# Accumulator_DC-DC.net
KiCad netlist of a schematic drawn in Altium Designer
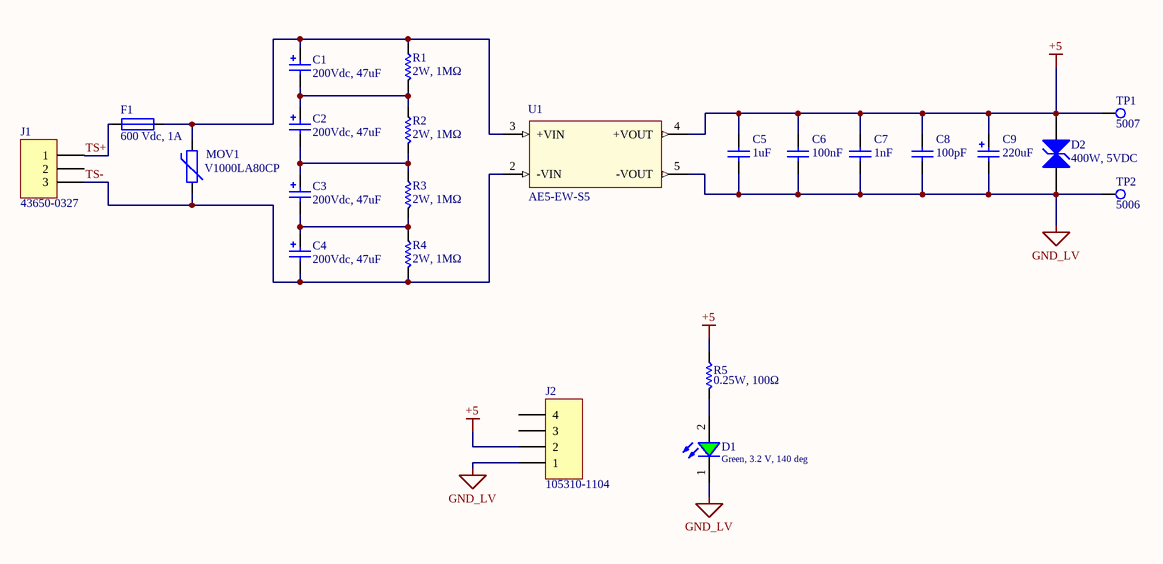
[diagram p0: Accumulator_DC-DC.SchDoc]

(export (version "E")
  (design (tool "Eeschema 10.0.6"))
  (components
    (comp (ref "C1")
      (value "200Vdc, 47uF")
      (footprint "WCAP-AT1H_13x20x5")
      (description "WCAP-AT1H Aluminum Electrolytic Capacitors, size Ф13x20mm, 200V DC, 47uF")
      (fields (field (name "PART NUMBER") "860241078002") (field (name "PUBLISHER") "Wurth Elektronik"))
      (libsource (lib "Components_Library") (part "860241078002"))
    )
    (comp (ref "C2")
      (value "200Vdc, 47uF")
      (footprint "WCAP-AT1H_13x20x5")
      (description "WCAP-AT1H Aluminum Electrolytic Capacitors, size Ф13x20mm, 200V DC, 47uF")
      (fields (field (name "PART NUMBER") "860241078002") (field (name "PUBLISHER") "Wurth Elektronik"))
      (libsource (lib "Components_Library") (part "860241078002"))
    )
    (comp (ref "C3")
      (value "200Vdc, 47uF")
      (footprint "WCAP-AT1H_13x20x5")
      (description "WCAP-AT1H Aluminum Electrolytic Capacitors, size Ф13x20mm, 200V DC, 47uF")
      (fields (field (name "PART NUMBER") "860241078002") (field (name "PUBLISHER") "Wurth Elektronik"))
      (libsource (lib "Components_Library") (part "860241078002"))
    )
    (comp (ref "C4")
      (value "200Vdc, 47uF")
      (footprint "WCAP-AT1H_13x20x5")
      (description "WCAP-AT1H Aluminum Electrolytic Capacitors, size Ф13x20mm, 200V DC, 47uF")
      (fields (field (name "PART NUMBER") "860241078002") (field (name "PUBLISHER") "Wurth Elektronik"))
      (libsource (lib "Components_Library") (part "860241078002"))
    )
    (comp (ref "C5")
      (value "1uF")
      (footprint "1206_3.2x1.6x1.15mm")
      (description "WCAP-CSGP Ceramic Capacitors, 1206, X7R, 10V, 1uF")
      (fields (field (name "PART NUMBER") "885012208013") (field (name "MANUFACTURER") "Wurth Elektronik"))
      (libsource (lib "Components_Library") (part "885012208013"))
    )
    (comp (ref "C6")
      (value "100nF")
      (footprint "1206_3.2x1.6x0.8mm")
      (description "WCAP-CSGP Ceramic Capacitors, 1206, X7R, 10V, 100nF")
      (fields (field (name "PART NUMBER") "885012208009") (field (name "MANUFACTURER") "Wurth Elektronik"))
      (libsource (lib "Components_Library") (part "885012208009"))
    )
    (comp (ref "C7")
      (value "1nF")
      (footprint "1206_3.2x1.6x0.8mm")
      (description "WCAP-CSGP Ceramic Capacitors, 1206, X7R, 10V, 1nF")
      (fields (field (name "PART NUMBER") "885012208006") (field (name "MANUFACTURER") "Wurth Elektronik"))
      (libsource (lib "Components_Library") (part "885012208006"))
    )
    (comp (ref "C8")
      (value "100pF")
      (footprint "1206_3.2x1.6x0.8mm")
      (description "WCAP-CSGP Ceramic Capacitors, 1206, NP0, 10V, 100pF")
      (fields (field (name "PART NUMBER") "885012008004") (field (name "MANUFACTURER") "Wurth Elektronik"))
      (libsource (lib "Components_Library") (part "885012008004"))
    )
    (comp (ref "C9")
      (value "220uF")
      (footprint "WCAP-ATG8_6.3x11x2.5")
      (description "WCAP-ATG8 Aluminum Electrolytic Capacitors, 6.3x11mm, 10 Vdc, 220 uF")
      (fields (field (name "PART NUMBER") "860010273009") (field (name "MANUFACTURER") "Wurth Elektronik"))
      (libsource (lib "Components_Library") (part "860010273009"))
    )
    (comp (ref "D1")
      (value "Green, 3.2 V, 140 deg")
      (footprint "WL-SMCW_1206")
      (description "SMT Mono-color Chip LED Waterclear WL-SMCW, size 1206, Green, 3.2 V, 140 deg, 450 mcd")
      (fields (field (name "PART NUMBER") "150120GS75000") (field (name "PUBLISHER") "Wurth Elektronik"))
      (libsource (lib "Components_Library") (part "150120GS75000"))
    )
    (comp (ref "D2")
      (value "400W, 5VDC")
      (footprint "WE-TVSP_DO-214AC_Bidirectional")
      (description "WE-TVSP Power TVS Diode, size DO-214AC, Bidirectional, 400 W, 5 VDC")
      (fields (field (name "PART NUMBER") "824501500") (field (name "MANUFACTURER") "Wurth Elektronik"))
      (libsource (lib "Components_Library") (part "824501500"))
    )
    (comp (ref "F1")
      (value "600 Vdc, 1A")
      (footprint "485001")
      (description "485 Series Fuse")
      (fields (field (name "MANUFACTURER") "Littlefuse"))
      (libsource (lib "Components_Library") (part "485001"))
    )
    (comp (ref "J1")
      (value "43650-0327")
      (footprint "43650-0327")
      (description "Micro-Fit 3.0 Vertical Header, 3.00mm Pitch, Single Row, 3 Circuits, Black")
      (fields (field (name "MANUFACTURER") "Molex"))
      (libsource (lib "Components_Library") (part "43650-0327"))
    )
    (comp (ref "J2")
      (value "105310-1104")
      (footprint "105310-1104")
      (description "Nano-Fit Vertical Header, Through Hole, 2.50mm Pitch, Dual Row, 4 Circuits, Black")
      (fields (field (name "MANUFACTURER") "Molex"))
      (libsource (lib "Components_Library") (part "105310-1104"))
    )
    (comp (ref "MOV1")
      (value "V1000LA80CP")
      (footprint "V1000LA160CP")
      (description "C-III Varistor Series")
      (fields (field (name "MANUFACTURER") "Littlefuse"))
      (libsource (lib "Components_Library") (part "V1000LA80CP"))
    )
    (comp (ref "R1")
      (value "2W, 1MΩ")
      (footprint "CR2512")
      (description "High Power Anti-Surge Chip Resistor")
      (fields (field (name "MANUFACTURER") "Bourns"))
      (libsource (lib "Components_Library") (part "CRS2512-FX-1004ELF"))
    )
    (comp (ref "R2")
      (value "2W, 1MΩ")
      (footprint "CR2512")
      (description "High Power Anti-Surge Chip Resistor")
      (fields (field (name "MANUFACTURER") "Bourns"))
      (libsource (lib "Components_Library") (part "CRS2512-FX-1004ELF"))
    )
    (comp (ref "R3")
      (value "2W, 1MΩ")
      (footprint "CR2512")
      (description "High Power Anti-Surge Chip Resistor")
      (fields (field (name "MANUFACTURER") "Bourns"))
      (libsource (lib "Components_Library") (part "CRS2512-FX-1004ELF"))
    )
    (comp (ref "R4")
      (value "2W, 1MΩ")
      (footprint "CR2512")
      (description "High Power Anti-Surge Chip Resistor")
      (fields (field (name "MANUFACTURER") "Bourns"))
      (libsource (lib "Components_Library") (part "CRS2512-FX-1004ELF"))
    )
    (comp (ref "R5")
      (value "0.25W, 100Ω")
      (footprint "CR1206")
      (description "Chip Resistor")
      (fields (field (name "MANUFACTURER") "Bourns"))
      (libsource (lib "Components_Library") (part "CR1206-FX-1000ELF"))
    )
    (comp (ref "TP1")
      (value "5007")
      (footprint "5007")
      (description "Compact THM Test Point, White")
      (fields (field (name "MANUFACTURER") "Keystone Electronics"))
      (libsource (lib "Components_Library") (part "5007"))
    )
    (comp (ref "TP2")
      (value "5006")
      (footprint "5006")
      (description "Compact THM Test Point, Black")
      (fields (field (name "MANUFACTURER") "Keystone Electronics"))
      (libsource (lib "Components_Library") (part "5006"))
    )
    (comp (ref "U1")
      (value "AE5-EW-S5")
      (footprint "AE5-EW-S5")
      (description "Ultra Wide Voltage Input DC-DC Converter")
      (fields (field (name "MANUFACTURER") "CUI INC"))
      (libsource (lib "Components_Library") (part "AE5-EW-S5"))
    )
  )
  (nets
    (net (code "1") (name "+5") (class "Default")
      (node (ref "C5") (pin "2") (pinfunction "2_2") (pintype "passive"))
      (node (ref "C6") (pin "2") (pinfunction "2_2") (pintype "passive"))
      (node (ref "C7") (pin "2") (pinfunction "2_2") (pintype "passive"))
      (node (ref "C8") (pin "2") (pinfunction "2_2") (pintype "passive"))
      (node (ref "C9") (pin "1") (pinfunction "P_1") (pintype "passive"))
      (node (ref "D2") (pin "2") (pinfunction "C_2") (pintype "passive"))
      (node (ref "J2") (pin "2") (pinfunction "2_2") (pintype "passive"))
      (node (ref "R5") (pin "2") (pinfunction "2_2") (pintype "passive"))
      (node (ref "TP1") (pin "0") (pinfunction "0_0") (pintype "passive"))
      (node (ref "U1") (pin "4") (pinfunction "+VOUT_4") (pintype "output"))
    )
    (net (code "2") (name "/TS+") (class "Default")
      (node (ref "F1") (pin "1") (pinfunction "1_1") (pintype "passive"))
      (node (ref "J1") (pin "1") (pinfunction "1_1") (pintype "passive"))
    )
    (net (code "3") (name "/TS-") (class "Default")
      (node (ref "C4") (pin "2") (pinfunction "N_2") (pintype "passive"))
      (node (ref "J1") (pin "3") (pinfunction "3_3") (pintype "passive"))
      (node (ref "MOV1") (pin "1") (pinfunction "1_1") (pintype "passive"))
      (node (ref "R4") (pin "1") (pinfunction "1_1") (pintype "passive"))
      (node (ref "U1") (pin "2") (pinfunction "-VIN_2") (pintype "input"))
    )
    (net (code "4") (name "GND_LV") (class "Default")
      (node (ref "C5") (pin "1") (pinfunction "1_1") (pintype "passive"))
      (node (ref "C6") (pin "1") (pinfunction "1_1") (pintype "passive"))
      (node (ref "C7") (pin "1") (pinfunction "1_1") (pintype "passive"))
      (node (ref "C8") (pin "1") (pinfunction "1_1") (pintype "passive"))
      (node (ref "C9") (pin "2") (pinfunction "N_2") (pintype "passive"))
      (node (ref "D1") (pin "1") (pinfunction "K_1") (pintype "passive"))
      (node (ref "D2") (pin "1") (pinfunction "C_1") (pintype "passive"))
      (node (ref "J2") (pin "1") (pinfunction "1_1") (pintype "passive"))
      (node (ref "TP2") (pin "0") (pinfunction "0_0") (pintype "passive"))
      (node (ref "U1") (pin "5") (pinfunction "-VOUT_5") (pintype "output"))
    )
    (net (code "5") (name "Net-(C1-N)") (class "Default")
      (node (ref "C1") (pin "2") (pinfunction "N_2") (pintype "passive"))
      (node (ref "C2") (pin "1") (pinfunction "P_1") (pintype "passive"))
      (node (ref "R1") (pin "1") (pinfunction "1_1") (pintype "passive"))
      (node (ref "R2") (pin "2") (pinfunction "2_2") (pintype "passive"))
    )
    (net (code "6") (name "Net-(C1-P)") (class "Default")
      (node (ref "C1") (pin "1") (pinfunction "P_1") (pintype "passive"))
      (node (ref "F1") (pin "2") (pinfunction "2_2") (pintype "passive"))
      (node (ref "MOV1") (pin "2") (pinfunction "2_2") (pintype "passive"))
      (node (ref "R1") (pin "2") (pinfunction "2_2") (pintype "passive"))
      (node (ref "U1") (pin "3") (pinfunction "+VIN_3") (pintype "input"))
    )
    (net (code "7") (name "Net-(C2-N)") (class "Default")
      (node (ref "C2") (pin "2") (pinfunction "N_2") (pintype "passive"))
      (node (ref "C3") (pin "1") (pinfunction "P_1") (pintype "passive"))
      (node (ref "R2") (pin "1") (pinfunction "1_1") (pintype "passive"))
      (node (ref "R3") (pin "2") (pinfunction "2_2") (pintype "passive"))
    )
    (net (code "8") (name "Net-(C3-N)") (class "Default")
      (node (ref "C3") (pin "2") (pinfunction "N_2") (pintype "passive"))
      (node (ref "C4") (pin "1") (pinfunction "P_1") (pintype "passive"))
      (node (ref "R3") (pin "1") (pinfunction "1_1") (pintype "passive"))
      (node (ref "R4") (pin "2") (pinfunction "2_2") (pintype "passive"))
    )
    (net (code "9") (name "Net-(D1-A)") (class "Default")
      (node (ref "D1") (pin "2") (pinfunction "A_2") (pintype "passive"))
      (node (ref "R5") (pin "1") (pinfunction "1_1") (pintype "passive"))
    )
    (net (code "10") (name "unconnected-(J1-Pad2)") (class "Default")
      (node (ref "J1") (pin "2") (pinfunction "2_2") (pintype "passive"))
    )
    (net (code "11") (name "unconnected-(J2-Pad3)") (class "Default")
      (node (ref "J2") (pin "3") (pinfunction "3_3") (pintype "passive"))
    )
    (net (code "12") (name "unconnected-(J2-Pad4)") (class "Default")
      (node (ref "J2") (pin "4") (pinfunction "4_4") (pintype "passive"))
    )
  )
)
